# Jonathan_ESC.net
KiCad netlist of a schematic drawn in Altium Designer
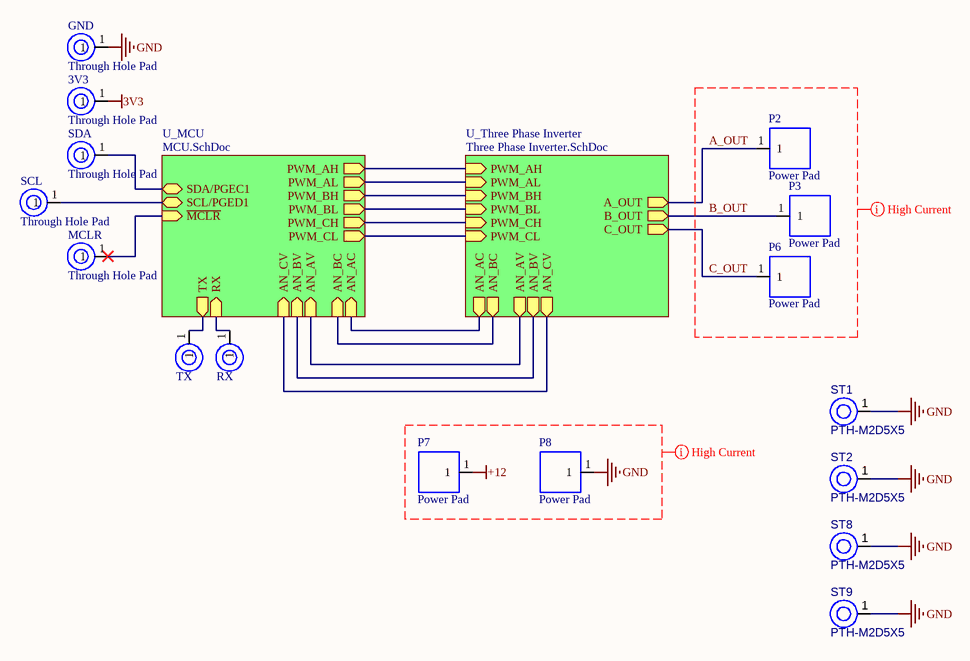
[diagram p0: Jonathan ESC.SchDoc]

(export (version "E")
  (design (tool "Eeschema 10.0.6"))
  (components
    (comp (ref "3V3")
      (value "Through Hole Pad")
      (footprint "THROUGH HOLE PAD")
      (libsource (lib "Schematic Library") (part "Through Hole Pad"))
    )
    (comp (ref "GND")
      (value "Through Hole Pad")
      (footprint "THROUGH HOLE PAD")
      (libsource (lib "Schematic Library") (part "Through Hole Pad"))
    )
    (comp (ref "MCLR")
      (value "Through Hole Pad")
      (footprint "THROUGH HOLE PAD")
      (libsource (lib "Schematic Library") (part "Through Hole Pad"))
    )
    (comp (ref "P2")
      (value "Power Pad")
      (footprint "Power Pad")
      (libsource (lib "Schematic Library") (part "Power Pad"))
    )
    (comp (ref "P3")
      (value "Power Pad")
      (footprint "Power Pad")
      (libsource (lib "Schematic Library") (part "Power Pad"))
    )
    (comp (ref "P6")
      (value "Power Pad")
      (footprint "Power Pad")
      (libsource (lib "Schematic Library") (part "Power Pad"))
    )
    (comp (ref "P7")
      (value "Power Pad")
      (footprint "Power Pad")
      (libsource (lib "Schematic Library") (part "Power Pad"))
    )
    (comp (ref "P8")
      (value "Power Pad")
      (footprint "Power Pad")
      (libsource (lib "Schematic Library") (part "Power Pad"))
    )
    (comp (ref "RX")
      (value "RX")
      (footprint "THROUGH HOLE PAD")
      (libsource (lib "Schematic Library") (part "Through Hole Pad"))
    )
    (comp (ref "SCL")
      (value "Through Hole Pad")
      (footprint "THROUGH HOLE PAD")
      (libsource (lib "Schematic Library") (part "Through Hole Pad"))
    )
    (comp (ref "SDA")
      (value "Through Hole Pad")
      (footprint "THROUGH HOLE PAD")
      (libsource (lib "Schematic Library") (part "Through Hole Pad"))
    )
    (comp (ref "ST1")
      (value "PTH-M2D5X5")
      (footprint "PTH-M2D5X5")
      (description "M2 PTH (2.5mm), 5mm pad")
      (libsource (lib "Blueshift Robotics") (part "CMP-00028-00000-1"))
    )
    (comp (ref "ST2")
      (value "PTH-M2D5X5")
      (footprint "PTH-M2D5X5")
      (description "M2 PTH (2.5mm), 5mm pad")
      (libsource (lib "Blueshift Robotics") (part "CMP-00028-00000-1"))
    )
    (comp (ref "ST8")
      (value "PTH-M2D5X5")
      (footprint "PTH-M2D5X5")
      (description "M2 PTH (2.5mm), 5mm pad")
      (libsource (lib "Blueshift Robotics") (part "CMP-00028-00000-1"))
    )
    (comp (ref "ST9")
      (value "PTH-M2D5X5")
      (footprint "PTH-M2D5X5")
      (description "M2 PTH (2.5mm), 5mm pad")
      (libsource (lib "Blueshift Robotics") (part "CMP-00028-00000-1"))
    )
    (comp (ref "TX")
      (value "TX")
      (footprint "THROUGH HOLE PAD")
      (libsource (lib "Schematic Library") (part "Through Hole Pad"))
    )
  )
  (nets
    (net (code "1") (name "+12") (class "Default")
      (node (ref "P7") (pin "1") (pinfunction "1_1") (pintype "passive"))
    )
    (net (code "7") (name "/A_OUT") (class "Default")
      (node (ref "P2") (pin "1") (pinfunction "1_1") (pintype "passive"))
    )
    (net (code "8") (name "/B_OUT") (class "Default")
      (node (ref "P3") (pin "1") (pinfunction "1_1") (pintype "passive"))
    )
    (net (code "9") (name "/C_OUT") (class "Default")
      (node (ref "P6") (pin "1") (pinfunction "1_1") (pintype "passive"))
    )
    (net (code "16") (name "/RX") (class "Default")
      (node (ref "RX") (pin "1") (pinfunction "1_1") (pintype "passive"))
    )
    (net (code "17") (name "/SCL{slash}PGED1") (class "Default")
      (node (ref "SCL") (pin "1") (pinfunction "1_1") (pintype "passive"))
    )
    (net (code "18") (name "/SDA{slash}PGEC1") (class "Default")
      (node (ref "SDA") (pin "1") (pinfunction "1_1") (pintype "passive"))
    )
    (net (code "19") (name "/TX") (class "Default")
      (node (ref "TX") (pin "1") (pinfunction "1_1") (pintype "passive"))
    )
    (net (code "20") (name "/~{MCLR}") (class "Default")
      (node (ref "MCLR") (pin "1") (pinfunction "1_1") (pintype "passive+no_connect"))
    )
    (net (code "21") (name "3V3") (class "Default")
      (node (ref "3V3") (pin "1") (pinfunction "1_1") (pintype "passive"))
    )
    (net (code "22") (name "GND") (class "Default")
      (node (ref "GND") (pin "1") (pinfunction "1_1") (pintype "passive"))
      (node (ref "P8") (pin "1") (pinfunction "1_1") (pintype "passive"))
      (node (ref "ST1") (pin "1") (pinfunction "H1_1") (pintype "passive"))
      (node (ref "ST2") (pin "1") (pinfunction "H1_1") (pintype "passive"))
      (node (ref "ST8") (pin "1") (pinfunction "H1_1") (pintype "passive"))
      (node (ref "ST9") (pin "1") (pinfunction "H1_1") (pintype "passive"))
    )
  )
)
